# sch_Connet_IMU.net
KiCad netlist of a schematic drawn in Altium Designer
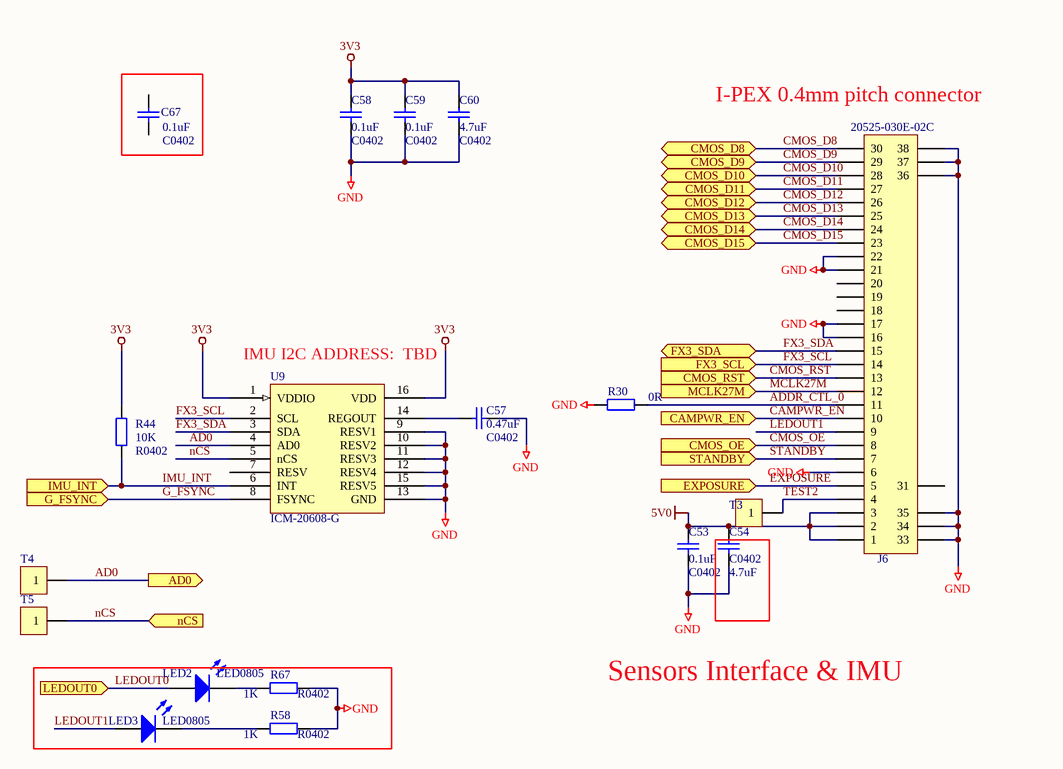
[diagram p0: sch_Connet&IMU.SchDoc]

(export (version "E")
  (design (tool "Eeschema 10.0.6"))
  (components
    (comp (ref "C53")
      (value "0.1uF")
      (footprint "0402C")
      (description "Capacitor")
      (fields (field (name "ALTIUM_VALUE") "C0402") (field (name "PUBLISHER") "Altium Limited"))
      (libsource (lib "Miscellaneous Devices") (part "Cap"))
    )
    (comp (ref "C54")
      (value "4.7uF")
      (footprint "0402C")
      (description "Capacitor")
      (fields (field (name "ALTIUM_VALUE") "C0402") (field (name "PUBLISHER") "Altium Limited"))
      (libsource (lib "Miscellaneous Devices") (part "Cap"))
    )
    (comp (ref "C57")
      (value "0.47uF")
      (footprint "0402C")
      (description "Capacitor")
      (fields (field (name "ALTIUM_VALUE") "C0402") (field (name "PUBLISHER") "Altium Limited"))
      (libsource (lib "Miscellaneous Devices") (part "Cap"))
    )
    (comp (ref "C58")
      (value "0.1uF")
      (footprint "0402C")
      (description "Capacitor")
      (fields (field (name "ALTIUM_VALUE") "C0402") (field (name "PUBLISHER") "Altium Limited"))
      (libsource (lib "Miscellaneous Devices") (part "Cap"))
    )
    (comp (ref "C59")
      (value "0.1uF")
      (footprint "0402C")
      (description "Capacitor")
      (fields (field (name "ALTIUM_VALUE") "C0402") (field (name "PUBLISHER") "Altium Limited"))
      (libsource (lib "Miscellaneous Devices") (part "Cap"))
    )
    (comp (ref "C60")
      (value "4.7uF")
      (footprint "0402C")
      (description "Capacitor")
      (fields (field (name "ALTIUM_VALUE") "C0402") (field (name "PUBLISHER") "Altium Limited"))
      (libsource (lib "Miscellaneous Devices") (part "Cap"))
    )
    (comp (ref "C67")
      (value "0.1uF")
      (footprint "0402C")
      (description "Capacitor")
      (fields (field (name "ALTIUM_VALUE") "C0402") (field (name "PUBLISHER") "Altium Limited"))
      (libsource (lib "Miscellaneous Devices") (part "Cap"))
    )
    (comp (ref "J6")
      (value "20525-030E-02C")
      (footprint "HSA30_P40L196W42H10_20525")
      (libsource (lib "SZG") (part "20525-030E-02C"))
    )
    (comp (ref "LED2")
      (value "LED0805")
      (footprint "LED0805A_L210W100H60")
      (description "发光二级管")
      (libsource (lib "TXW") (part "LED"))
    )
    (comp (ref "LED3")
      (value "LED0805")
      (footprint "LED0805A_L210W100H60")
      (description "发光二级管")
      (libsource (lib "TXW") (part "LED"))
    )
    (comp (ref "R30")
      (value "0R")
      (footprint "0402R")
      (description "Resistor")
      (fields (field (name "PUBLISHER") "Altium Limited"))
      (libsource (lib "Miscellaneous Devices") (part "Res2"))
    )
    (comp (ref "R44")
      (value "10K")
      (footprint "0402R")
      (description "Resistor")
      (fields (field (name "ALTIUM_VALUE") "R0402") (field (name "PUBLISHER") "Altium Limited"))
      (libsource (lib "") (part "Res2_1"))
    )
    (comp (ref "R58")
      (value "1K")
      (footprint "0402R")
      (description "Resistor")
      (fields (field (name "ALTIUM_VALUE") "R0402") (field (name "PUBLISHER") "Altium Limited"))
      (libsource (lib "Miscellaneous Devices") (part "Res2"))
    )
    (comp (ref "R67")
      (value "1K")
      (footprint "0402R")
      (description "Resistor")
      (fields (field (name "ALTIUM_VALUE") "R0402") (field (name "PUBLISHER") "Altium Limited"))
      (libsource (lib "Miscellaneous Devices") (part "Res2"))
    )
    (comp (ref "T3")
      (value "CON1")
      (footprint "PAD_TP_D1.2")
      (description "Connector")
      (libsource (lib "SuperSchLib") (part "CON1"))
    )
    (comp (ref "T4")
      (value "CON1")
      (footprint "PAD_TP_D1.2")
      (description "Connector")
      (libsource (lib "SuperSchLib") (part "CON1"))
    )
    (comp (ref "T5")
      (value "CON1")
      (footprint "PAD_TP_D1.2")
      (description "Connector")
      (libsource (lib "SuperSchLib") (part "CON1"))
    )
    (comp (ref "U9")
      (value "ICM-20608-G")
      (footprint "LGA16_P50L30W30H08")
      (libsource (lib "SZG") (part "ICM-20608-G"))
    )
  )
  (nets
    (net (code "1") (name "/AD0") (class "Default")
      (node (ref "T4") (pin "1") (pinfunction "1_1") (pintype "passive"))
      (node (ref "U9") (pin "4") (pinfunction "AD0_4") (pintype "passive"))
    )
    (net (code "2") (name "/ADDR_CTL_0") (class "Default")
      (node (ref "J6") (pin "11") (pinfunction "11_11") (pintype "passive"))
      (node (ref "R30") (pin "1") (pinfunction "1_1") (pintype "passive"))
    )
    (net (code "3") (name "/CAMPWR_EN") (class "Default")
      (node (ref "J6") (pin "10") (pinfunction "10_10") (pintype "passive"))
    )
    (net (code "4") (name "/CMOS_D8") (class "Default")
      (node (ref "J6") (pin "30") (pinfunction "30_30") (pintype "passive"))
    )
    (net (code "5") (name "/CMOS_D9") (class "Default")
      (node (ref "J6") (pin "29") (pinfunction "29_29") (pintype "passive"))
    )
    (net (code "6") (name "/CMOS_D10") (class "Default")
      (node (ref "J6") (pin "28") (pinfunction "28_28") (pintype "passive"))
    )
    (net (code "7") (name "/CMOS_D11") (class "Default")
      (node (ref "J6") (pin "27") (pinfunction "27_27") (pintype "passive"))
    )
    (net (code "8") (name "/CMOS_D12") (class "Default")
      (node (ref "J6") (pin "26") (pinfunction "26_26") (pintype "passive"))
    )
    (net (code "9") (name "/CMOS_D13") (class "Default")
      (node (ref "J6") (pin "25") (pinfunction "25_25") (pintype "passive"))
    )
    (net (code "10") (name "/CMOS_D14") (class "Default")
      (node (ref "J6") (pin "24") (pinfunction "24_24") (pintype "passive"))
    )
    (net (code "11") (name "/CMOS_D15") (class "Default")
      (node (ref "J6") (pin "23") (pinfunction "23_23") (pintype "passive"))
    )
    (net (code "12") (name "/CMOS_OE") (class "Default")
      (node (ref "J6") (pin "8") (pinfunction "8_8") (pintype "passive"))
    )
    (net (code "13") (name "/CMOS_RST") (class "Default")
      (node (ref "J6") (pin "13") (pinfunction "13_13") (pintype "passive"))
    )
    (net (code "14") (name "/EXPOSURE") (class "Default")
      (node (ref "J6") (pin "5") (pinfunction "5_5") (pintype "passive"))
    )
    (net (code "15") (name "/FX3_SCL") (class "Default")
      (node (ref "J6") (pin "14") (pinfunction "14_14") (pintype "passive"))
      (node (ref "U9") (pin "2") (pinfunction "SCL_2") (pintype "passive"))
    )
    (net (code "16") (name "/FX3_SDA") (class "Default")
      (node (ref "J6") (pin "15") (pinfunction "15_15") (pintype "passive"))
      (node (ref "U9") (pin "3") (pinfunction "SDA_3") (pintype "passive"))
    )
    (net (code "17") (name "/G_FSYNC") (class "Default")
      (node (ref "U9") (pin "8") (pinfunction "FSYNC_8") (pintype "passive"))
    )
    (net (code "18") (name "/IMU_INT") (class "Default")
      (node (ref "R44") (pin "1") (pinfunction "1_1") (pintype "passive"))
      (node (ref "U9") (pin "6") (pinfunction "INT_6") (pintype "passive"))
    )
    (net (code "19") (name "/LEDOUT0") (class "Default")
      (node (ref "LED2") (pin "1") (pinfunction "A_1") (pintype "passive"))
    )
    (net (code "20") (name "/LEDOUT1") (class "Default")
      (node (ref "J6") (pin "9") (pinfunction "9_9") (pintype "passive"))
      (node (ref "LED3") (pin "1") (pinfunction "A_1") (pintype "passive"))
    )
    (net (code "21") (name "/MCLK27M") (class "Default")
      (node (ref "J6") (pin "12") (pinfunction "12_12") (pintype "passive"))
    )
    (net (code "22") (name "/STANDBY") (class "Default")
      (node (ref "J6") (pin "7") (pinfunction "7_7") (pintype "passive"))
    )
    (net (code "23") (name "/TEST2") (class "Default")
      (node (ref "J6") (pin "4") (pinfunction "4_4") (pintype "passive"))
      (node (ref "T3") (pin "1") (pinfunction "1_1") (pintype "passive"))
    )
    (net (code "24") (name "/nCS") (class "Default")
      (node (ref "T5") (pin "1") (pinfunction "1_1") (pintype "passive"))
      (node (ref "U9") (pin "5") (pinfunction "nCS_5") (pintype "passive"))
    )
    (net (code "25") (name "3V3") (class "Default")
      (node (ref "C58") (pin "2") (pinfunction "2_2") (pintype "passive"))
      (node (ref "C59") (pin "2") (pinfunction "2_2") (pintype "passive"))
      (node (ref "C60") (pin "2") (pinfunction "2_2") (pintype "passive"))
      (node (ref "R44") (pin "2") (pinfunction "2_2") (pintype "passive"))
      (node (ref "U9") (pin "1") (pinfunction "VDDIO_1") (pintype "input"))
      (node (ref "U9") (pin "16") (pinfunction "VDD_16") (pintype "passive"))
    )
    (net (code "26") (name "5V0") (class "Default")
      (node (ref "C53") (pin "2") (pinfunction "2_2") (pintype "passive"))
      (node (ref "C54") (pin "2") (pinfunction "2_2") (pintype "passive"))
      (node (ref "J6") (pin "1") (pinfunction "1_1") (pintype "passive"))
      (node (ref "J6") (pin "2") (pinfunction "2_2") (pintype "passive"))
      (node (ref "J6") (pin "3") (pinfunction "3_3") (pintype "passive"))
    )
    (net (code "27") (name "GND") (class "Default")
      (node (ref "C53") (pin "1") (pinfunction "1_1") (pintype "passive"))
      (node (ref "C54") (pin "1") (pinfunction "1_1") (pintype "passive"))
      (node (ref "C57") (pin "1") (pinfunction "1_1") (pintype "passive"))
      (node (ref "C58") (pin "1") (pinfunction "1_1") (pintype "passive"))
      (node (ref "C59") (pin "1") (pinfunction "1_1") (pintype "passive"))
      (node (ref "C60") (pin "1") (pinfunction "1_1") (pintype "passive"))
      (node (ref "J6") (pin "16") (pinfunction "16_16") (pintype "passive"))
      (node (ref "J6") (pin "17") (pinfunction "17_17") (pintype "passive"))
      (node (ref "J6") (pin "21") (pinfunction "21_21") (pintype "passive"))
      (node (ref "J6") (pin "22") (pinfunction "22_22") (pintype "passive"))
      (node (ref "J6") (pin "33") (pinfunction "33_33") (pintype "passive"))
      (node (ref "J6") (pin "34") (pinfunction "34_34") (pintype "passive"))
      (node (ref "J6") (pin "35") (pinfunction "35_35") (pintype "passive"))
      (node (ref "J6") (pin "36") (pinfunction "36_36") (pintype "passive"))
      (node (ref "J6") (pin "37") (pinfunction "37_37") (pintype "passive"))
      (node (ref "J6") (pin "38") (pinfunction "38_38") (pintype "passive"))
      (node (ref "J6") (pin "6") (pinfunction "6_6") (pintype "passive"))
      (node (ref "R30") (pin "2") (pinfunction "2_2") (pintype "passive"))
      (node (ref "R58") (pin "1") (pinfunction "1_1") (pintype "passive"))
      (node (ref "R67") (pin "1") (pinfunction "1_1") (pintype "passive"))
      (node (ref "U9") (pin "10") (pinfunction "RESV2_10") (pintype "passive"))
      (node (ref "U9") (pin "11") (pinfunction "RESV3_11") (pintype "passive"))
      (node (ref "U9") (pin "12") (pinfunction "RESV4_12") (pintype "passive"))
      (node (ref "U9") (pin "13") (pinfunction "GND_13") (pintype "passive"))
      (node (ref "U9") (pin "15") (pinfunction "RESV5_15") (pintype "passive"))
      (node (ref "U9") (pin "9") (pinfunction "RESV1_9") (pintype "passive"))
    )
    (net (code "28") (name "Net-(LED2-K)") (class "Default")
      (node (ref "LED2") (pin "2") (pinfunction "K_2") (pintype "passive"))
      (node (ref "R67") (pin "2") (pinfunction "2_2") (pintype "passive"))
    )
    (net (code "29") (name "Net-(LED3-K)") (class "Default")
      (node (ref "LED3") (pin "2") (pinfunction "K_2") (pintype "passive"))
      (node (ref "R58") (pin "2") (pinfunction "2_2") (pintype "passive"))
    )
    (net (code "30") (name "Net-(U9-REGOUT)") (class "Default")
      (node (ref "C57") (pin "2") (pinfunction "2_2") (pintype "passive"))
      (node (ref "U9") (pin "14") (pinfunction "REGOUT_14") (pintype "passive"))
    )
    (net (code "31") (name "unconnected-(C67-Pad1)") (class "Default")
      (node (ref "C67") (pin "1") (pinfunction "1_1") (pintype "passive"))
    )
    (net (code "32") (name "unconnected-(C67-Pad2)") (class "Default")
      (node (ref "C67") (pin "2") (pinfunction "2_2") (pintype "passive"))
    )
    (net (code "33") (name "unconnected-(J6-Pad18)") (class "Default")
      (node (ref "J6") (pin "18") (pinfunction "18_18") (pintype "passive"))
    )
    (net (code "34") (name "unconnected-(J6-Pad19)") (class "Default")
      (node (ref "J6") (pin "19") (pinfunction "19_19") (pintype "passive"))
    )
    (net (code "35") (name "unconnected-(J6-Pad20)") (class "Default")
      (node (ref "J6") (pin "20") (pinfunction "20_20") (pintype "passive"))
    )
    (net (code "36") (name "unconnected-(J6-Pad31)") (class "Default")
      (node (ref "J6") (pin "31") (pinfunction "31_31") (pintype "passive"))
    )
    (net (code "37") (name "unconnected-(U9-RESV-Pad7)") (class "Default")
      (node (ref "U9") (pin "7") (pinfunction "RESV_7") (pintype "passive"))
    )
  )
)
